# STB_Spectrometer.net
KiCad netlist of a schematic drawn in Altium Designer
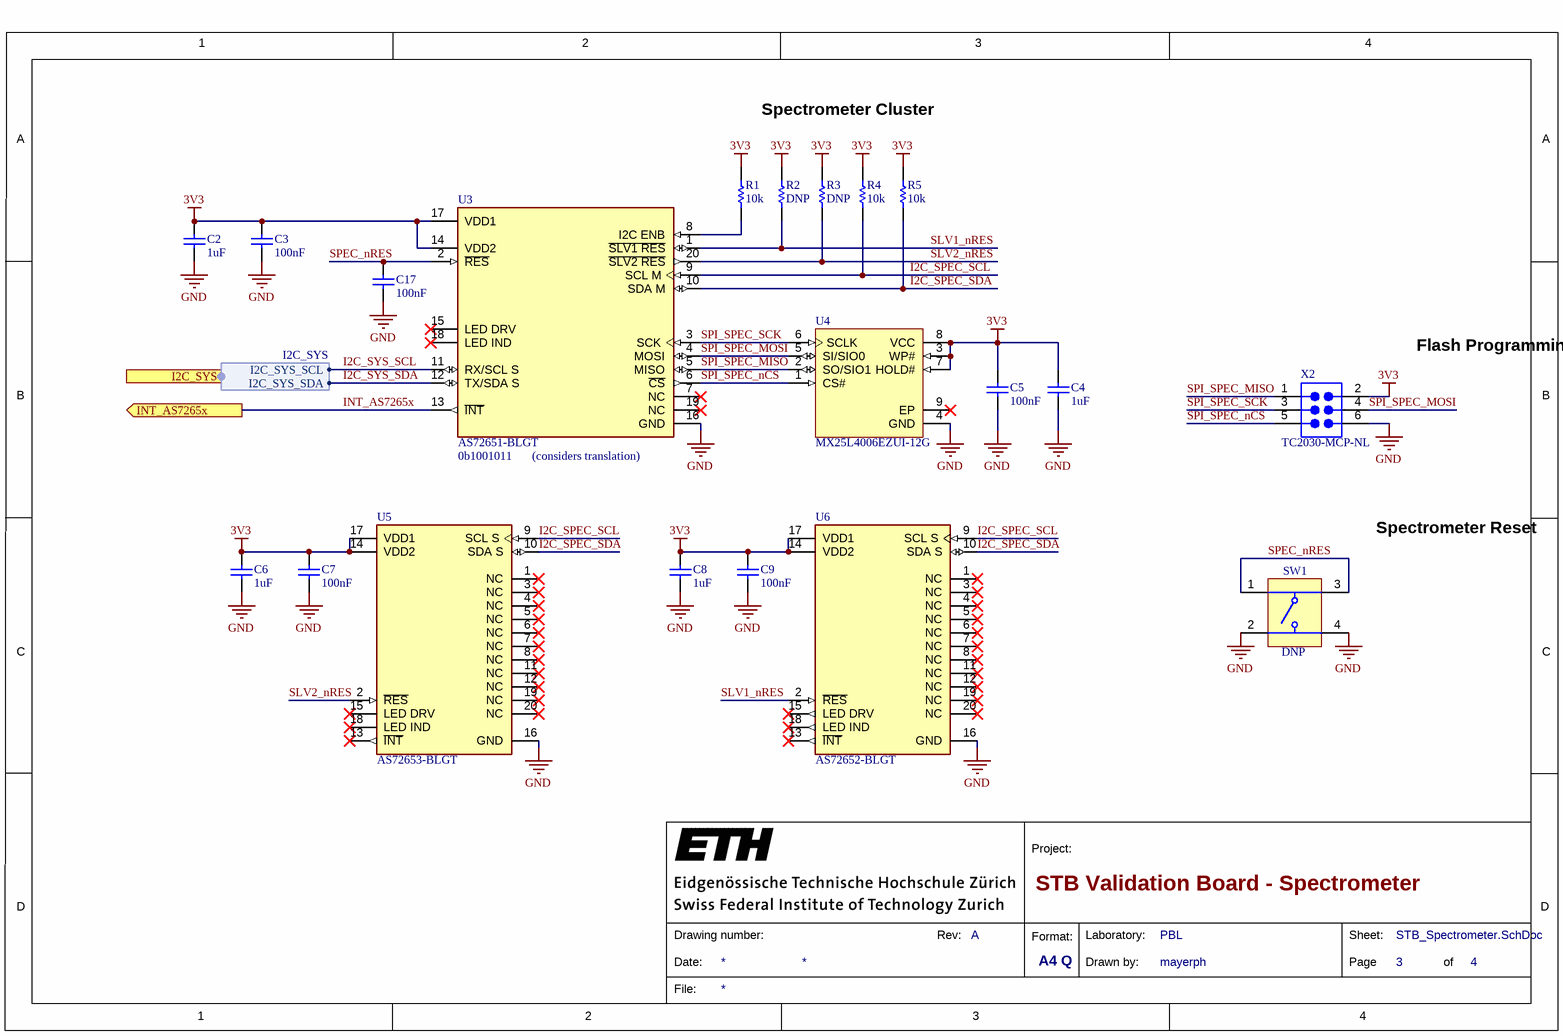
[diagram p0: STB_Spectrometer.SchDoc]

(export (version "E")
  (design (tool "Eeschema 10.0.6"))
  (components
    (comp (ref "C2")
      (value "1uF")
      (footprint "CAPC1608X90X35LL15T15")
      (fields (field (name "MANUFACTURER") "Kemet") (field (name "PART NUMBER") "C0603C105K4RACTU"))
      (libsource (lib "Altium Content Vault") (part "CAP"))
    )
    (comp (ref "C3")
      (value "100nF")
      (footprint "CAPC1050X55X23LL05T13")
      (description "Chip Capacitor, 100 nF, +/- 10%, 16 V, -55 to 125 degC, 0402 (1005 Metric), RoHS, Tape and Reel")
      (fields
        (field (name "MANUFACTURER") "Samsung Electro-Mechanics")
        (field (name "MANUFACTURER PART NUMBER") "CL05B104KO5NNNC")
      )
      (libsource (lib "Altium Content Vault") (part "CAP-NP-2"))
    )
    (comp (ref "C4")
      (value "1uF")
      (footprint "CAPC1608X90X35LL15T15")
      (fields (field (name "MANUFACTURER") "Kemet") (field (name "PART NUMBER") "C0603C105K4RACTU"))
      (libsource (lib "Altium Content Vault") (part "CAP"))
    )
    (comp (ref "C5")
      (value "100nF")
      (footprint "CAPC1050X55X23LL05T13")
      (description "Chip Capacitor, 100 nF, +/- 10%, 16 V, -55 to 125 degC, 0402 (1005 Metric), RoHS, Tape and Reel")
      (fields
        (field (name "MANUFACTURER") "Samsung Electro-Mechanics")
        (field (name "MANUFACTURER PART NUMBER") "CL05B104KO5NNNC")
      )
      (libsource (lib "Altium Content Vault") (part "CAP-NP-2"))
    )
    (comp (ref "C6")
      (value "1uF")
      (footprint "CAPC1608X90X35LL15T15")
      (fields (field (name "MANUFACTURER") "Kemet") (field (name "PART NUMBER") "C0603C105K4RACTU"))
      (libsource (lib "Altium Content Vault") (part "CAP"))
    )
    (comp (ref "C7")
      (value "100nF")
      (footprint "CAPC1050X55X23LL05T13")
      (description "Chip Capacitor, 100 nF, +/- 10%, 16 V, -55 to 125 degC, 0402 (1005 Metric), RoHS, Tape and Reel")
      (fields
        (field (name "MANUFACTURER") "Samsung Electro-Mechanics")
        (field (name "MANUFACTURER PART NUMBER") "CL05B104KO5NNNC")
      )
      (libsource (lib "Altium Content Vault") (part "CAP-NP-2"))
    )
    (comp (ref "C8")
      (value "1uF")
      (footprint "CAPC1608X90X35LL15T15")
      (fields (field (name "MANUFACTURER") "Kemet") (field (name "PART NUMBER") "C0603C105K4RACTU"))
      (libsource (lib "Altium Content Vault") (part "CAP"))
    )
    (comp (ref "C9")
      (value "100nF")
      (footprint "CAPC1050X55X23LL05T13")
      (description "Chip Capacitor, 100 nF, +/- 10%, 16 V, -55 to 125 degC, 0402 (1005 Metric), RoHS, Tape and Reel")
      (fields
        (field (name "MANUFACTURER") "Samsung Electro-Mechanics")
        (field (name "MANUFACTURER PART NUMBER") "CL05B104KO5NNNC")
      )
      (libsource (lib "Altium Content Vault") (part "CAP-NP-2"))
    )
    (comp (ref "C17")
      (value "100nF")
      (footprint "CAPC1050X55X23LL05T13")
      (description "Chip Capacitor, 100 nF, +/- 10%, 16 V, -55 to 125 degC, 0402 (1005 Metric), RoHS, Tape and Reel")
      (fields
        (field (name "MANUFACTURER") "Samsung Electro-Mechanics")
        (field (name "MANUFACTURER PART NUMBER") "CL05B104KO5NNNC")
      )
      (libsource (lib "Altium Content Vault") (part "CAP-NP-2"))
    )
    (comp (ref "R1")
      (value "10k")
      (footprint "RESC1005X40X25LL05T05")
      (description "Chip Resistor, 10 KOhm, +/- 1%, 0.1 W, -55 to 155 degC, 0402 (1005 Metric), RoHS, Tape and Reel")
      (fields (field (name "TOLERANCE") "1%") (field (name "MANUFACTURER") "Panasonic"))
      (libsource (lib "Altium Content Vault") (part "RES-2"))
    )
    (comp (ref "R2")
      (value "DNP")
      (footprint "RESC1005X40X25LL05T05")
      (description "Chip Resistor, 10 KOhm, +/- 1%, 0.1 W, -55 to 155 degC, 0402 (1005 Metric), RoHS, Tape and Reel")
      (fields (field (name "TOLERANCE") "1%") (field (name "MANUFACTURER") "Panasonic"))
      (libsource (lib "Altium Content Vault") (part "RES-2"))
    )
    (comp (ref "R3")
      (value "DNP")
      (footprint "RESC1005X40X25LL05T05")
      (description "Chip Resistor, 10 KOhm, +/- 1%, 0.1 W, -55 to 155 degC, 0402 (1005 Metric), RoHS, Tape and Reel")
      (fields (field (name "TOLERANCE") "1%") (field (name "MANUFACTURER") "Panasonic"))
      (libsource (lib "Altium Content Vault") (part "RES-2"))
    )
    (comp (ref "R4")
      (value "10k")
      (footprint "RESC1005X40X25LL05T05")
      (description "Chip Resistor, 10 KOhm, +/- 1%, 0.1 W, -55 to 155 degC, 0402 (1005 Metric), RoHS, Tape and Reel")
      (fields (field (name "TOLERANCE") "1%") (field (name "MANUFACTURER") "Panasonic"))
      (libsource (lib "Altium Content Vault") (part "RES-2"))
    )
    (comp (ref "R5")
      (value "10k")
      (footprint "RESC1005X40X25LL05T05")
      (description "Chip Resistor, 10 KOhm, +/- 1%, 0.1 W, -55 to 155 degC, 0402 (1005 Metric), RoHS, Tape and Reel")
      (fields (field (name "TOLERANCE") "1%") (field (name "MANUFACTURER") "Panasonic"))
      (libsource (lib "Altium Content Vault") (part "RES-2"))
    )
    (comp (ref "SW1")
      (value "DNP")
      (footprint "PNSC-EVPAA_V")
      (description "Light Touch Switch, 100 mOhm, -40 to 85 degC, 4-Pin SMD, RoHS, Tape and Reel")
      (fields (field (name "MANUFACTURER") "Panasonic") (field (name "PART NO") "EVP-AA002K"))
      (libsource (lib "Altium Content Vault") (part "SW-SPST-4"))
    )
    (comp (ref "U3")
      (value "AS72651-BLGT")
      (footprint "FP-AS72651-BLGT-MFG")
      (description "AS72651-BLGT LGA20 LF T&RDP")
      (fields (field (name "MANUFACTURER") "ams") (field (name "ADDRESS") "0b1001011"))
      (libsource (lib "Altium Content Vault") (part "96c49a94035c55414f36293780c885a"))
    )
    (comp (ref "U4")
      (value "MX25L4006EZUI-12G")
      (footprint "MXIC-USON-8_V")
      (description "4 M-Bit [x1 / x2] CMOS Serial Flash, 86 MHz, -0.7 to 3.6 V, -40 to 85 degC, Body  2 x 3 x 0.6 mm")
      (fields (field (name "MANUFACTURER") "Macronix"))
      (libsource (lib "Altium Content Vault") (part "MXIC-MX25L4006EZUI-12G-USON-8"))
    )
    (comp (ref "U5")
      (value "AS72653-BLGT")
      (footprint "FP-AS72653-BLGT-MFG")
      (description "AS72653-BLGT LGA20 LF T&RDP")
      (fields (field (name "MANUFACTURER") "ams"))
      (libsource (lib "Altium Content Vault") (part "dbaf3b1d840af62113c8d089df4a8dc"))
    )
    (comp (ref "U6")
      (value "AS72652-BLGT")
      (footprint "FP-AS72652-BLGT-MFG")
      (description "AS72652-BLGT LGA20 LF T&RDP")
      (fields (field (name "MANUFACTURER") "ams"))
      (libsource (lib "Altium Content Vault") (part "071b443b34d8799e7ba01a9bef9e0b3"))
    )
    (comp (ref "X2")
      (value "TC2030-MCP-NL")
      (footprint "TC2030-MCP-NL")
      (description "CABLE, TAG CONNECT, WITH OUT LEG, FOR IC")
      (libsource (lib "ETHZ Vault") (part "CON-3x2-Male"))
    )
  )
  (nets
    (net (code "2") (name "/I2C_SPEC_SCL") (class "Default")
      (node (ref "R4") (pin "1") (pinfunction "1_1") (pintype "passive"))
      (node (ref "U3") (pin "9") (pinfunction "SCL_M_9") (pintype "input"))
      (node (ref "U5") (pin "9") (pinfunction "SCL_S_9") (pintype "input"))
      (node (ref "U6") (pin "9") (pinfunction "SCL_S_9") (pintype "input"))
    )
    (net (code "3") (name "/I2C_SPEC_SDA") (class "Default")
      (node (ref "R5") (pin "1") (pinfunction "1_1") (pintype "passive"))
      (node (ref "U3") (pin "10") (pinfunction "SDA_M_10") (pintype "bidirectional"))
      (node (ref "U5") (pin "10") (pinfunction "SDA_S_10") (pintype "bidirectional"))
      (node (ref "U6") (pin "10") (pinfunction "SDA_S_10") (pintype "bidirectional"))
    )
    (net (code "4") (name "/I2C_SYS_SCL") (class "Default")
      (node (ref "U3") (pin "11") (pinfunction "RX/SCL_S_11") (pintype "bidirectional"))
    )
    (net (code "5") (name "/I2C_SYS_SDA") (class "Default")
      (node (ref "U3") (pin "12") (pinfunction "TX/SDA_S_12") (pintype "bidirectional"))
    )
    (net (code "6") (name "/INT_AS7265x") (class "Default")
      (node (ref "U3") (pin "13") (pinfunction "~{INT}_13") (pintype "output"))
    )
    (net (code "7") (name "/SLV1_nRES") (class "Default")
      (node (ref "R2") (pin "1") (pinfunction "1_1") (pintype "passive"))
      (node (ref "U3") (pin "1") (pinfunction "~{SLV1_RES}_1") (pintype "bidirectional"))
      (node (ref "U6") (pin "2") (pinfunction "~{RES}_2") (pintype "input"))
    )
    (net (code "8") (name "/SLV2_nRES") (class "Default")
      (node (ref "R3") (pin "1") (pinfunction "1_1") (pintype "passive"))
      (node (ref "U3") (pin "20") (pinfunction "~{SLV2_RES}_20") (pintype "output"))
      (node (ref "U5") (pin "2") (pinfunction "~{RES}_2") (pintype "input"))
    )
    (net (code "9") (name "/SPEC_nRES") (class "Default")
      (node (ref "C17") (pin "2") (pinfunction "2_2") (pintype "passive"))
      (node (ref "SW1") (pin "1") (pinfunction "A_1") (pintype "passive"))
      (node (ref "SW1") (pin "3") (pinfunction "A'_3") (pintype "passive"))
      (node (ref "U3") (pin "2") (pinfunction "~{RES}_2") (pintype "input"))
    )
    (net (code "10") (name "/SPI_SPEC_MISO") (class "Default")
      (node (ref "U3") (pin "5") (pinfunction "MISO_5") (pintype "bidirectional"))
      (node (ref "U4") (pin "2") (pinfunction "SO/SIO1_2") (pintype "bidirectional"))
      (node (ref "X2") (pin "1") (pinfunction "1_1") (pintype "passive"))
    )
    (net (code "11") (name "/SPI_SPEC_MOSI") (class "Default")
      (node (ref "U3") (pin "4") (pinfunction "MOSI_4") (pintype "bidirectional"))
      (node (ref "U4") (pin "5") (pinfunction "SI/SIO0_5") (pintype "bidirectional"))
      (node (ref "X2") (pin "4") (pinfunction "4_4") (pintype "passive"))
    )
    (net (code "12") (name "/SPI_SPEC_SCK") (class "Default")
      (node (ref "U3") (pin "3") (pinfunction "SCK_3") (pintype "input"))
      (node (ref "U4") (pin "6") (pinfunction "SCLK_6") (pintype "input"))
      (node (ref "X2") (pin "3") (pinfunction "3_3") (pintype "passive"))
    )
    (net (code "13") (name "/SPI_SPEC_nCS") (class "Default")
      (node (ref "U3") (pin "6") (pinfunction "~{CS}_6") (pintype "output"))
      (node (ref "U4") (pin "1") (pinfunction "CS#_1") (pintype "input"))
      (node (ref "X2") (pin "5") (pinfunction "5_5") (pintype "passive"))
    )
    (net (code "15") (name "3V3") (class "Default")
      (node (ref "C2") (pin "2") (pinfunction "2_2") (pintype "passive"))
      (node (ref "C3") (pin "2") (pinfunction "2_2") (pintype "passive"))
      (node (ref "C4") (pin "2") (pinfunction "2_2") (pintype "passive"))
      (node (ref "C5") (pin "2") (pinfunction "2_2") (pintype "passive"))
      (node (ref "C6") (pin "2") (pinfunction "2_2") (pintype "passive"))
      (node (ref "C7") (pin "2") (pinfunction "2_2") (pintype "passive"))
      (node (ref "C8") (pin "2") (pinfunction "2_2") (pintype "passive"))
      (node (ref "C9") (pin "2") (pinfunction "2_2") (pintype "passive"))
      (node (ref "R1") (pin "2") (pinfunction "2_2") (pintype "passive"))
      (node (ref "R2") (pin "2") (pinfunction "2_2") (pintype "passive"))
      (node (ref "R3") (pin "2") (pinfunction "2_2") (pintype "passive"))
      (node (ref "R4") (pin "2") (pinfunction "2_2") (pintype "passive"))
      (node (ref "R5") (pin "2") (pinfunction "2_2") (pintype "passive"))
      (node (ref "U3") (pin "14") (pinfunction "VDD2_14") (pintype "power_in"))
      (node (ref "U3") (pin "17") (pinfunction "VDD1_17") (pintype "power_in"))
      (node (ref "U4") (pin "3") (pinfunction "WP#_3") (pintype "input"))
      (node (ref "U4") (pin "7") (pinfunction "HOLD#_7") (pintype "input"))
      (node (ref "U4") (pin "8") (pinfunction "VCC_8") (pintype "power_in"))
      (node (ref "U5") (pin "14") (pinfunction "VDD2_14") (pintype "power_in"))
      (node (ref "U5") (pin "17") (pinfunction "VDD1_17") (pintype "power_in"))
      (node (ref "U6") (pin "14") (pinfunction "VDD2_14") (pintype "power_in"))
      (node (ref "U6") (pin "17") (pinfunction "VDD1_17") (pintype "power_in"))
      (node (ref "X2") (pin "2") (pinfunction "2_2") (pintype "passive"))
    )
    (net (code "16") (name "GND") (class "Default")
      (node (ref "C17") (pin "1") (pinfunction "1_1") (pintype "passive"))
      (node (ref "C2") (pin "1") (pinfunction "1_1") (pintype "passive"))
      (node (ref "C3") (pin "1") (pinfunction "1_1") (pintype "passive"))
      (node (ref "C4") (pin "1") (pinfunction "1_1") (pintype "passive"))
      (node (ref "C5") (pin "1") (pinfunction "1_1") (pintype "passive"))
      (node (ref "C6") (pin "1") (pinfunction "1_1") (pintype "passive"))
      (node (ref "C7") (pin "1") (pinfunction "1_1") (pintype "passive"))
      (node (ref "C8") (pin "1") (pinfunction "1_1") (pintype "passive"))
      (node (ref "C9") (pin "1") (pinfunction "1_1") (pintype "passive"))
      (node (ref "SW1") (pin "2") (pinfunction "B_2") (pintype "passive"))
      (node (ref "SW1") (pin "4") (pinfunction "B'_4") (pintype "passive"))
      (node (ref "U3") (pin "16") (pinfunction "GND_16") (pintype "power_in"))
      (node (ref "U4") (pin "4") (pinfunction "GND_4") (pintype "power_in"))
      (node (ref "U5") (pin "16") (pinfunction "GND_16") (pintype "power_in"))
      (node (ref "U6") (pin "16") (pinfunction "GND_16") (pintype "power_in"))
      (node (ref "X2") (pin "6") (pinfunction "6_6") (pintype "passive"))
    )
    (net (code "17") (name "Net-(U3-I2C_ENB)") (class "Default")
      (node (ref "R1") (pin "1") (pinfunction "1_1") (pintype "passive"))
      (node (ref "U3") (pin "8") (pinfunction "I2C_ENB_8") (pintype "input"))
    )
    (net (code "18") (name "unconnected-(U3-LED_DRV-Pad15)") (class "Default")
      (node (ref "U3") (pin "15") (pinfunction "LED_DRV_15") (pintype "passive+no_connect"))
    )
    (net (code "19") (name "unconnected-(U3-LED_IND-Pad18)") (class "Default")
      (node (ref "U3") (pin "18") (pinfunction "LED_IND_18") (pintype "passive+no_connect"))
    )
    (net (code "20") (name "unconnected-(U3-NC-Pad7)") (class "Default")
      (node (ref "U3") (pin "7") (pinfunction "NC_7") (pintype "passive+no_connect"))
    )
    (net (code "21") (name "unconnected-(U3-NC-Pad19)") (class "Default")
      (node (ref "U3") (pin "19") (pinfunction "NC_19") (pintype "passive+no_connect"))
    )
    (net (code "22") (name "unconnected-(U4-EP-Pad9)") (class "Default")
      (node (ref "U4") (pin "9") (pinfunction "EP_9") (pintype "passive+no_connect"))
    )
    (net (code "23") (name "unconnected-(U5-LED_DRV-Pad15)") (class "Default")
      (node (ref "U5") (pin "15") (pinfunction "LED_DRV_15") (pintype "passive+no_connect"))
    )
    (net (code "24") (name "unconnected-(U5-LED_IND-Pad18)") (class "Default")
      (node (ref "U5") (pin "18") (pinfunction "LED_IND_18") (pintype "passive+no_connect"))
    )
    (net (code "25") (name "unconnected-(U5-NC-Pad1)") (class "Default")
      (node (ref "U5") (pin "1") (pinfunction "NC_1") (pintype "passive+no_connect"))
    )
    (net (code "26") (name "unconnected-(U5-NC-Pad3)") (class "Default")
      (node (ref "U5") (pin "3") (pinfunction "NC_3") (pintype "passive+no_connect"))
    )
    (net (code "27") (name "unconnected-(U5-NC-Pad4)") (class "Default")
      (node (ref "U5") (pin "4") (pinfunction "NC_4") (pintype "passive+no_connect"))
    )
    (net (code "28") (name "unconnected-(U5-NC-Pad5)") (class "Default")
      (node (ref "U5") (pin "5") (pinfunction "NC_5") (pintype "passive+no_connect"))
    )
    (net (code "29") (name "unconnected-(U5-NC-Pad6)") (class "Default")
      (node (ref "U5") (pin "6") (pinfunction "NC_6") (pintype "passive+no_connect"))
    )
    (net (code "30") (name "unconnected-(U5-NC-Pad7)") (class "Default")
      (node (ref "U5") (pin "7") (pinfunction "NC_7") (pintype "passive+no_connect"))
    )
    (net (code "31") (name "unconnected-(U5-NC-Pad8)") (class "Default")
      (node (ref "U5") (pin "8") (pinfunction "NC_8") (pintype "passive+no_connect"))
    )
    (net (code "32") (name "unconnected-(U5-NC-Pad11)") (class "Default")
      (node (ref "U5") (pin "11") (pinfunction "NC_11") (pintype "passive+no_connect"))
    )
    (net (code "33") (name "unconnected-(U5-NC-Pad12)") (class "Default")
      (node (ref "U5") (pin "12") (pinfunction "NC_12") (pintype "passive+no_connect"))
    )
    (net (code "34") (name "unconnected-(U5-NC-Pad19)") (class "Default")
      (node (ref "U5") (pin "19") (pinfunction "NC_19") (pintype "passive+no_connect"))
    )
    (net (code "35") (name "unconnected-(U5-NC-Pad20)") (class "Default")
      (node (ref "U5") (pin "20") (pinfunction "NC_20") (pintype "passive+no_connect"))
    )
    (net (code "36") (name "unconnected-(U5-~{INT}-Pad13)") (class "Default")
      (node (ref "U5") (pin "13") (pinfunction "~{INT}_13") (pintype "output+no_connect"))
    )
    (net (code "37") (name "unconnected-(U6-LED_DRV-Pad15)") (class "Default")
      (node (ref "U6") (pin "15") (pinfunction "LED_DRV_15") (pintype "output+no_connect"))
    )
    (net (code "38") (name "unconnected-(U6-LED_IND-Pad18)") (class "Default")
      (node (ref "U6") (pin "18") (pinfunction "LED_IND_18") (pintype "output+no_connect"))
    )
    (net (code "39") (name "unconnected-(U6-NC-Pad1)") (class "Default")
      (node (ref "U6") (pin "1") (pinfunction "NC_1") (pintype "passive+no_connect"))
    )
    (net (code "40") (name "unconnected-(U6-NC-Pad3)") (class "Default")
      (node (ref "U6") (pin "3") (pinfunction "NC_3") (pintype "passive+no_connect"))
    )
    (net (code "41") (name "unconnected-(U6-NC-Pad4)") (class "Default")
      (node (ref "U6") (pin "4") (pinfunction "NC_4") (pintype "passive+no_connect"))
    )
    (net (code "42") (name "unconnected-(U6-NC-Pad5)") (class "Default")
      (node (ref "U6") (pin "5") (pinfunction "NC_5") (pintype "passive+no_connect"))
    )
    (net (code "43") (name "unconnected-(U6-NC-Pad6)") (class "Default")
      (node (ref "U6") (pin "6") (pinfunction "NC_6") (pintype "passive+no_connect"))
    )
    (net (code "44") (name "unconnected-(U6-NC-Pad7)") (class "Default")
      (node (ref "U6") (pin "7") (pinfunction "NC_7") (pintype "passive+no_connect"))
    )
    (net (code "45") (name "unconnected-(U6-NC-Pad8)") (class "Default")
      (node (ref "U6") (pin "8") (pinfunction "NC_8") (pintype "passive+no_connect"))
    )
    (net (code "46") (name "unconnected-(U6-NC-Pad11)") (class "Default")
      (node (ref "U6") (pin "11") (pinfunction "NC_11") (pintype "passive+no_connect"))
    )
    (net (code "47") (name "unconnected-(U6-NC-Pad12)") (class "Default")
      (node (ref "U6") (pin "12") (pinfunction "NC_12") (pintype "passive+no_connect"))
    )
    (net (code "48") (name "unconnected-(U6-NC-Pad19)") (class "Default")
      (node (ref "U6") (pin "19") (pinfunction "NC_19") (pintype "passive+no_connect"))
    )
    (net (code "49") (name "unconnected-(U6-NC-Pad20)") (class "Default")
      (node (ref "U6") (pin "20") (pinfunction "NC_20") (pintype "passive+no_connect"))
    )
    (net (code "50") (name "unconnected-(U6-~{INT}-Pad13)") (class "Default")
      (node (ref "U6") (pin "13") (pinfunction "~{INT}_13") (pintype "output+no_connect"))
    )
  )
)
